# quad7seg.net
KiCad netlist of a schematic drawn in EAGLE
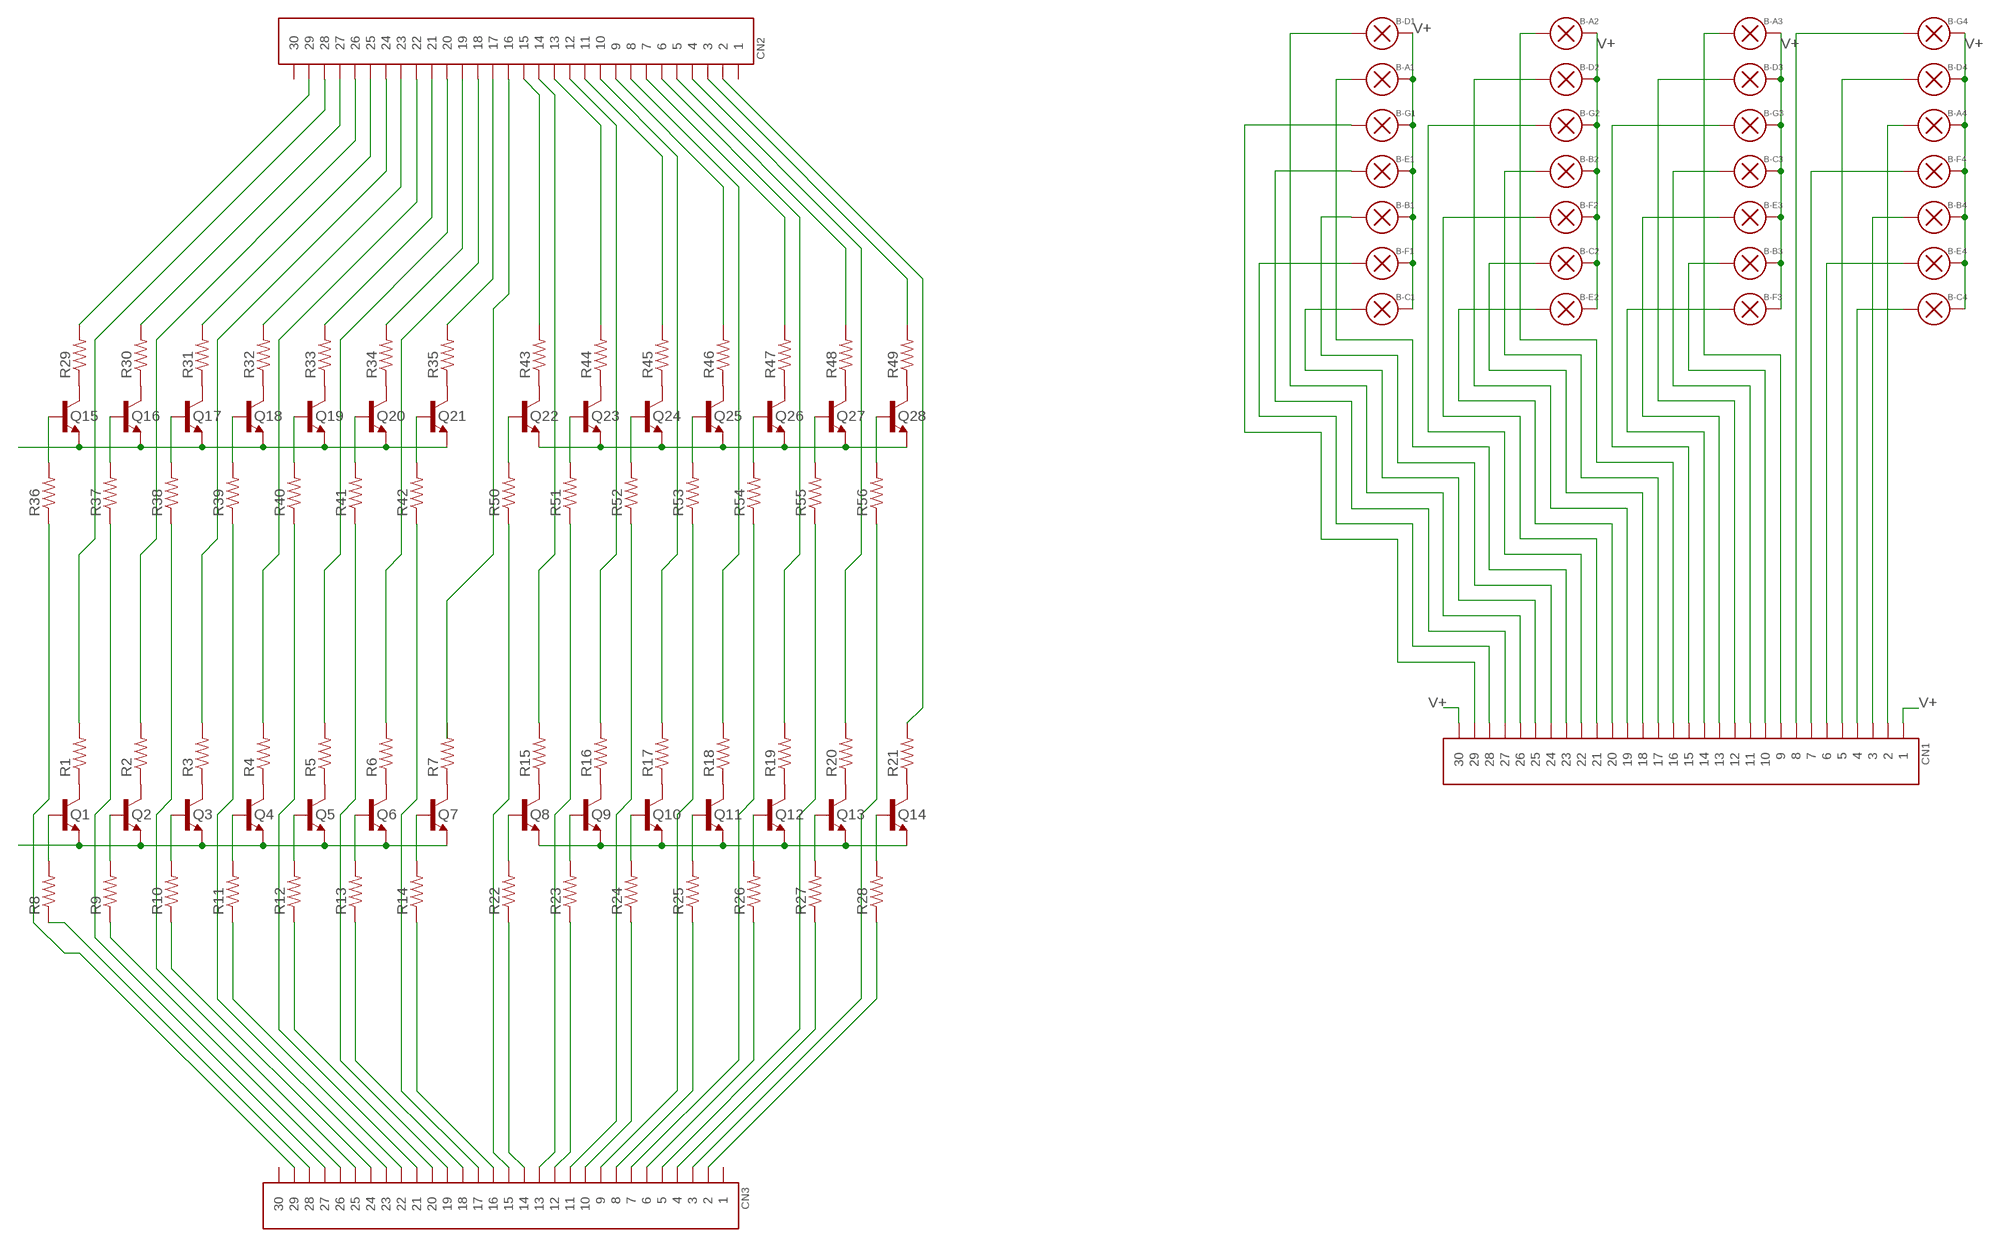
[diagram p0: schematic, sheet 1]

(export (version "E")
  (design (tool "Eeschema 10.0.6"))
  (components
    (comp (ref "B-A1")
      (value "BULB-N")
      (footprint "eagle-import:4X11BULB1")
      (libsource (lib "eagle-import") (part "BULB-N"))
    )
    (comp (ref "B-A2")
      (value "BULB-N")
      (footprint "eagle-import:4X11BULB1")
      (libsource (lib "eagle-import") (part "BULB-N"))
    )
    (comp (ref "B-A3")
      (value "BULB-N")
      (footprint "eagle-import:4X11BULB1")
      (libsource (lib "eagle-import") (part "BULB-N"))
    )
    (comp (ref "B-A4")
      (value "BULB-N")
      (footprint "eagle-import:4X11BULB1")
      (libsource (lib "eagle-import") (part "BULB-N"))
    )
    (comp (ref "B-B1")
      (value "BULB-F")
      (footprint "eagle-import:4X11BULB2")
      (libsource (lib "eagle-import") (part "BULB-F"))
    )
    (comp (ref "B-B2")
      (value "BULB-F")
      (footprint "eagle-import:4X11BULB2")
      (libsource (lib "eagle-import") (part "BULB-F"))
    )
    (comp (ref "B-B3")
      (value "BULB-F")
      (footprint "eagle-import:4X11BULB2")
      (libsource (lib "eagle-import") (part "BULB-F"))
    )
    (comp (ref "B-B4")
      (value "BULB-F")
      (footprint "eagle-import:4X11BULB2")
      (libsource (lib "eagle-import") (part "BULB-F"))
    )
    (comp (ref "B-C1")
      (value "BULB-F")
      (footprint "eagle-import:4X11BULB2")
      (libsource (lib "eagle-import") (part "BULB-F"))
    )
    (comp (ref "B-C2")
      (value "BULB-F")
      (footprint "eagle-import:4X11BULB2")
      (libsource (lib "eagle-import") (part "BULB-F"))
    )
    (comp (ref "B-C3")
      (value "BULB-F")
      (footprint "eagle-import:4X11BULB2")
      (libsource (lib "eagle-import") (part "BULB-F"))
    )
    (comp (ref "B-C4")
      (value "BULB-F")
      (footprint "eagle-import:4X11BULB2")
      (libsource (lib "eagle-import") (part "BULB-F"))
    )
    (comp (ref "B-D1")
      (value "BULB-N")
      (footprint "eagle-import:4X11BULB1")
      (libsource (lib "eagle-import") (part "BULB-N"))
    )
    (comp (ref "B-D2")
      (value "BULB-N")
      (footprint "eagle-import:4X11BULB1")
      (libsource (lib "eagle-import") (part "BULB-N"))
    )
    (comp (ref "B-D3")
      (value "BULB-N")
      (footprint "eagle-import:4X11BULB1")
      (libsource (lib "eagle-import") (part "BULB-N"))
    )
    (comp (ref "B-D4")
      (value "BULB-N")
      (footprint "eagle-import:4X11BULB1")
      (libsource (lib "eagle-import") (part "BULB-N"))
    )
    (comp (ref "B-E1")
      (value "BULB-F")
      (footprint "eagle-import:4X11BULB2")
      (libsource (lib "eagle-import") (part "BULB-F"))
    )
    (comp (ref "B-E2")
      (value "BULB-F")
      (footprint "eagle-import:4X11BULB2")
      (libsource (lib "eagle-import") (part "BULB-F"))
    )
    (comp (ref "B-E3")
      (value "BULB-F")
      (footprint "eagle-import:4X11BULB2")
      (libsource (lib "eagle-import") (part "BULB-F"))
    )
    (comp (ref "B-E4")
      (value "BULB-F")
      (footprint "eagle-import:4X11BULB2")
      (libsource (lib "eagle-import") (part "BULB-F"))
    )
    (comp (ref "B-F1")
      (value "BULB-F")
      (footprint "eagle-import:4X11BULB2")
      (libsource (lib "eagle-import") (part "BULB-F"))
    )
    (comp (ref "B-F2")
      (value "BULB-F")
      (footprint "eagle-import:4X11BULB2")
      (libsource (lib "eagle-import") (part "BULB-F"))
    )
    (comp (ref "B-F3")
      (value "BULB-F")
      (footprint "eagle-import:4X11BULB2")
      (libsource (lib "eagle-import") (part "BULB-F"))
    )
    (comp (ref "B-F4")
      (value "BULB-F")
      (footprint "eagle-import:4X11BULB2")
      (libsource (lib "eagle-import") (part "BULB-F"))
    )
    (comp (ref "B-G1")
      (value "BULB-N")
      (footprint "eagle-import:4X11BULB1")
      (libsource (lib "eagle-import") (part "BULB-N"))
    )
    (comp (ref "B-G2")
      (value "BULB-N")
      (footprint "eagle-import:4X11BULB1")
      (libsource (lib "eagle-import") (part "BULB-N"))
    )
    (comp (ref "B-G3")
      (value "BULB-N")
      (footprint "eagle-import:4X11BULB1")
      (libsource (lib "eagle-import") (part "BULB-N"))
    )
    (comp (ref "B-G4")
      (value "BULB-N")
      (footprint "eagle-import:4X11BULB1")
      (libsource (lib "eagle-import") (part "BULB-N"))
    )
    (comp (ref "CN1")
      (value "HD30")
      (footprint "eagle-import:HD30")
      (libsource (lib "eagle-import") (part "HD30"))
    )
    (comp (ref "CN2")
      (value "HD30")
      (footprint "eagle-import:HD30")
      (libsource (lib "eagle-import") (part "HD30"))
    )
    (comp (ref "CN3")
      (value "HD30")
      (footprint "eagle-import:HD30")
      (libsource (lib "eagle-import") (part "HD30"))
    )
    (comp (ref "Q1")
      (value "2N3904-1")
      (footprint "eagle-import:TO92BH")
      (libsource (lib "eagle-import") (part "2N3904-1"))
    )
    (comp (ref "Q2")
      (value "2N3904-1")
      (footprint "eagle-import:TO92BH")
      (libsource (lib "eagle-import") (part "2N3904-1"))
    )
    (comp (ref "Q3")
      (value "2N3904-1")
      (footprint "eagle-import:TO92BH")
      (libsource (lib "eagle-import") (part "2N3904-1"))
    )
    (comp (ref "Q4")
      (value "2N3904-1")
      (footprint "eagle-import:TO92BH")
      (libsource (lib "eagle-import") (part "2N3904-1"))
    )
    (comp (ref "Q5")
      (value "2N3904-1")
      (footprint "eagle-import:TO92BH")
      (libsource (lib "eagle-import") (part "2N3904-1"))
    )
    (comp (ref "Q6")
      (value "2N3904-1")
      (footprint "eagle-import:TO92BH")
      (libsource (lib "eagle-import") (part "2N3904-1"))
    )
    (comp (ref "Q7")
      (value "2N3904-1")
      (footprint "eagle-import:TO92BH")
      (libsource (lib "eagle-import") (part "2N3904-1"))
    )
    (comp (ref "Q8")
      (value "2N3904-1")
      (footprint "eagle-import:TO92BH")
      (libsource (lib "eagle-import") (part "2N3904-1"))
    )
    (comp (ref "Q9")
      (value "2N3904-1")
      (footprint "eagle-import:TO92BH")
      (libsource (lib "eagle-import") (part "2N3904-1"))
    )
    (comp (ref "Q10")
      (value "2N3904-1")
      (footprint "eagle-import:TO92BH")
      (libsource (lib "eagle-import") (part "2N3904-1"))
    )
    (comp (ref "Q11")
      (value "2N3904-1")
      (footprint "eagle-import:TO92BH")
      (libsource (lib "eagle-import") (part "2N3904-1"))
    )
    (comp (ref "Q12")
      (value "2N3904-1")
      (footprint "eagle-import:TO92BH")
      (libsource (lib "eagle-import") (part "2N3904-1"))
    )
    (comp (ref "Q13")
      (value "2N3904-1")
      (footprint "eagle-import:TO92BH")
      (libsource (lib "eagle-import") (part "2N3904-1"))
    )
    (comp (ref "Q14")
      (value "2N3904-1")
      (footprint "eagle-import:TO92BH")
      (libsource (lib "eagle-import") (part "2N3904-1"))
    )
    (comp (ref "Q15")
      (value "2N3904-1")
      (footprint "eagle-import:TO92BH")
      (libsource (lib "eagle-import") (part "2N3904-1"))
    )
    (comp (ref "Q16")
      (value "2N3904-1")
      (footprint "eagle-import:TO92BH")
      (libsource (lib "eagle-import") (part "2N3904-1"))
    )
    (comp (ref "Q17")
      (value "2N3904-1")
      (footprint "eagle-import:TO92BH")
      (libsource (lib "eagle-import") (part "2N3904-1"))
    )
    (comp (ref "Q18")
      (value "2N3904-1")
      (footprint "eagle-import:TO92BH")
      (libsource (lib "eagle-import") (part "2N3904-1"))
    )
    (comp (ref "Q19")
      (value "2N3904-1")
      (footprint "eagle-import:TO92BH")
      (libsource (lib "eagle-import") (part "2N3904-1"))
    )
    (comp (ref "Q20")
      (value "2N3904-1")
      (footprint "eagle-import:TO92BH")
      (libsource (lib "eagle-import") (part "2N3904-1"))
    )
    (comp (ref "Q21")
      (value "2N3904-1")
      (footprint "eagle-import:TO92BH")
      (libsource (lib "eagle-import") (part "2N3904-1"))
    )
    (comp (ref "Q22")
      (value "2N3904-1")
      (footprint "eagle-import:TO92BH")
      (libsource (lib "eagle-import") (part "2N3904-1"))
    )
    (comp (ref "Q23")
      (value "2N3904-1")
      (footprint "eagle-import:TO92BH")
      (libsource (lib "eagle-import") (part "2N3904-1"))
    )
    (comp (ref "Q24")
      (value "2N3904-1")
      (footprint "eagle-import:TO92BH")
      (libsource (lib "eagle-import") (part "2N3904-1"))
    )
    (comp (ref "Q25")
      (value "2N3904-1")
      (footprint "eagle-import:TO92BH")
      (libsource (lib "eagle-import") (part "2N3904-1"))
    )
    (comp (ref "Q26")
      (value "2N3904-1")
      (footprint "eagle-import:TO92BH")
      (libsource (lib "eagle-import") (part "2N3904-1"))
    )
    (comp (ref "Q27")
      (value "2N3904-1")
      (footprint "eagle-import:TO92BH")
      (libsource (lib "eagle-import") (part "2N3904-1"))
    )
    (comp (ref "Q28")
      (value "2N3904-1")
      (footprint "eagle-import:TO92BH")
      (libsource (lib "eagle-import") (part "2N3904-1"))
    )
    (comp (ref "R1")
      (value "R1/8-7.6MM")
      (footprint "eagle-import:R0125-7.6")
      (libsource (lib "eagle-import") (part "R1/8-7.6MM"))
    )
    (comp (ref "R2")
      (value "R1/8-7.6MM")
      (footprint "eagle-import:R0125-7.6")
      (libsource (lib "eagle-import") (part "R1/8-7.6MM"))
    )
    (comp (ref "R3")
      (value "R1/8-7.6MM")
      (footprint "eagle-import:R0125-7.6")
      (libsource (lib "eagle-import") (part "R1/8-7.6MM"))
    )
    (comp (ref "R4")
      (value "R1/8-7.6MM")
      (footprint "eagle-import:R0125-7.6")
      (libsource (lib "eagle-import") (part "R1/8-7.6MM"))
    )
    (comp (ref "R5")
      (value "R1/8-7.6MM")
      (footprint "eagle-import:R0125-7.6")
      (libsource (lib "eagle-import") (part "R1/8-7.6MM"))
    )
    (comp (ref "R6")
      (value "R1/8-7.6MM")
      (footprint "eagle-import:R0125-7.6")
      (libsource (lib "eagle-import") (part "R1/8-7.6MM"))
    )
    (comp (ref "R7")
      (value "R1/8-7.6MM")
      (footprint "eagle-import:R0125-7.6")
      (libsource (lib "eagle-import") (part "R1/8-7.6MM"))
    )
    (comp (ref "R8")
      (value "R1/8-7.6MM")
      (footprint "eagle-import:R0125-7.6")
      (libsource (lib "eagle-import") (part "R1/8-7.6MM"))
    )
    (comp (ref "R9")
      (value "R1/8-7.6MM")
      (footprint "eagle-import:R0125-7.6")
      (libsource (lib "eagle-import") (part "R1/8-7.6MM"))
    )
    (comp (ref "R10")
      (value "R1/8-7.6MM")
      (footprint "eagle-import:R0125-7.6")
      (libsource (lib "eagle-import") (part "R1/8-7.6MM"))
    )
    (comp (ref "R11")
      (value "R1/8-7.6MM")
      (footprint "eagle-import:R0125-7.6")
      (libsource (lib "eagle-import") (part "R1/8-7.6MM"))
    )
    (comp (ref "R12")
      (value "R1/8-7.6MM")
      (footprint "eagle-import:R0125-7.6")
      (libsource (lib "eagle-import") (part "R1/8-7.6MM"))
    )
    (comp (ref "R13")
      (value "R1/8-7.6MM")
      (footprint "eagle-import:R0125-7.6")
      (libsource (lib "eagle-import") (part "R1/8-7.6MM"))
    )
    (comp (ref "R14")
      (value "R1/8-7.6MM")
      (footprint "eagle-import:R0125-7.6")
      (libsource (lib "eagle-import") (part "R1/8-7.6MM"))
    )
    (comp (ref "R15")
      (value "R1/8-7.6MM")
      (footprint "eagle-import:R0125-7.6")
      (libsource (lib "eagle-import") (part "R1/8-7.6MM"))
    )
    (comp (ref "R16")
      (value "R1/8-7.6MM")
      (footprint "eagle-import:R0125-7.6")
      (libsource (lib "eagle-import") (part "R1/8-7.6MM"))
    )
    (comp (ref "R17")
      (value "R1/8-7.6MM")
      (footprint "eagle-import:R0125-7.6")
      (libsource (lib "eagle-import") (part "R1/8-7.6MM"))
    )
    (comp (ref "R18")
      (value "R1/8-7.6MM")
      (footprint "eagle-import:R0125-7.6")
      (libsource (lib "eagle-import") (part "R1/8-7.6MM"))
    )
    (comp (ref "R19")
      (value "R1/8-7.6MM")
      (footprint "eagle-import:R0125-7.6")
      (libsource (lib "eagle-import") (part "R1/8-7.6MM"))
    )
    (comp (ref "R20")
      (value "R1/8-7.6MM")
      (footprint "eagle-import:R0125-7.6")
      (libsource (lib "eagle-import") (part "R1/8-7.6MM"))
    )
    (comp (ref "R21")
      (value "R1/8-7.6MM")
      (footprint "eagle-import:R0125-7.6")
      (libsource (lib "eagle-import") (part "R1/8-7.6MM"))
    )
    (comp (ref "R22")
      (value "R1/8-7.6MM")
      (footprint "eagle-import:R0125-7.6")
      (libsource (lib "eagle-import") (part "R1/8-7.6MM"))
    )
    (comp (ref "R23")
      (value "R1/8-7.6MM")
      (footprint "eagle-import:R0125-7.6")
      (libsource (lib "eagle-import") (part "R1/8-7.6MM"))
    )
    (comp (ref "R24")
      (value "R1/8-7.6MM")
      (footprint "eagle-import:R0125-7.6")
      (libsource (lib "eagle-import") (part "R1/8-7.6MM"))
    )
    (comp (ref "R25")
      (value "R1/8-7.6MM")
      (footprint "eagle-import:R0125-7.6")
      (libsource (lib "eagle-import") (part "R1/8-7.6MM"))
    )
    (comp (ref "R26")
      (value "R1/8-7.6MM")
      (footprint "eagle-import:R0125-7.6")
      (libsource (lib "eagle-import") (part "R1/8-7.6MM"))
    )
    (comp (ref "R27")
      (value "R1/8-7.6MM")
      (footprint "eagle-import:R0125-7.6")
      (libsource (lib "eagle-import") (part "R1/8-7.6MM"))
    )
    (comp (ref "R28")
      (value "R1/8-7.6MM")
      (footprint "eagle-import:R0125-7.6")
      (libsource (lib "eagle-import") (part "R1/8-7.6MM"))
    )
    (comp (ref "R29")
      (value "R1/8-7.6MM")
      (footprint "eagle-import:R0125-7.6")
      (libsource (lib "eagle-import") (part "R1/8-7.6MM"))
    )
    (comp (ref "R30")
      (value "R1/8-7.6MM")
      (footprint "eagle-import:R0125-7.6")
      (libsource (lib "eagle-import") (part "R1/8-7.6MM"))
    )
    (comp (ref "R31")
      (value "R1/8-7.6MM")
      (footprint "eagle-import:R0125-7.6")
      (libsource (lib "eagle-import") (part "R1/8-7.6MM"))
    )
    (comp (ref "R32")
      (value "R1/8-7.6MM")
      (footprint "eagle-import:R0125-7.6")
      (libsource (lib "eagle-import") (part "R1/8-7.6MM"))
    )
    (comp (ref "R33")
      (value "R1/8-7.6MM")
      (footprint "eagle-import:R0125-7.6")
      (libsource (lib "eagle-import") (part "R1/8-7.6MM"))
    )
    (comp (ref "R34")
      (value "R1/8-7.6MM")
      (footprint "eagle-import:R0125-7.6")
      (libsource (lib "eagle-import") (part "R1/8-7.6MM"))
    )
    (comp (ref "R35")
      (value "R1/8-7.6MM")
      (footprint "eagle-import:R0125-7.6")
      (libsource (lib "eagle-import") (part "R1/8-7.6MM"))
    )
    (comp (ref "R36")
      (value "R1/8-7.6MM")
      (footprint "eagle-import:R0125-7.6")
      (libsource (lib "eagle-import") (part "R1/8-7.6MM"))
    )
    (comp (ref "R37")
      (value "R1/8-7.6MM")
      (footprint "eagle-import:R0125-7.6")
      (libsource (lib "eagle-import") (part "R1/8-7.6MM"))
    )
    (comp (ref "R38")
      (value "R1/8-7.6MM")
      (footprint "eagle-import:R0125-7.6")
      (libsource (lib "eagle-import") (part "R1/8-7.6MM"))
    )
    (comp (ref "R39")
      (value "R1/8-7.6MM")
      (footprint "eagle-import:R0125-7.6")
      (libsource (lib "eagle-import") (part "R1/8-7.6MM"))
    )
    (comp (ref "R40")
      (value "R1/8-7.6MM")
      (footprint "eagle-import:R0125-7.6")
      (libsource (lib "eagle-import") (part "R1/8-7.6MM"))
    )
    (comp (ref "R41")
      (value "R1/8-7.6MM")
      (footprint "eagle-import:R0125-7.6")
      (libsource (lib "eagle-import") (part "R1/8-7.6MM"))
    )
    (comp (ref "R42")
      (value "R1/8-7.6MM")
      (footprint "eagle-import:R0125-7.6")
      (libsource (lib "eagle-import") (part "R1/8-7.6MM"))
    )
    (comp (ref "R43")
      (value "R1/8-7.6MM")
      (footprint "eagle-import:R0125-7.6")
      (libsource (lib "eagle-import") (part "R1/8-7.6MM"))
    )
    (comp (ref "R44")
      (value "R1/8-7.6MM")
      (footprint "eagle-import:R0125-7.6")
      (libsource (lib "eagle-import") (part "R1/8-7.6MM"))
    )
    (comp (ref "R45")
      (value "R1/8-7.6MM")
      (footprint "eagle-import:R0125-7.6")
      (libsource (lib "eagle-import") (part "R1/8-7.6MM"))
    )
    (comp (ref "R46")
      (value "R1/8-7.6MM")
      (footprint "eagle-import:R0125-7.6")
      (libsource (lib "eagle-import") (part "R1/8-7.6MM"))
    )
    (comp (ref "R47")
      (value "R1/8-7.6MM")
      (footprint "eagle-import:R0125-7.6")
      (libsource (lib "eagle-import") (part "R1/8-7.6MM"))
    )
    (comp (ref "R48")
      (value "R1/8-7.6MM")
      (footprint "eagle-import:R0125-7.6")
      (libsource (lib "eagle-import") (part "R1/8-7.6MM"))
    )
    (comp (ref "R49")
      (value "R1/8-7.6MM")
      (footprint "eagle-import:R0125-7.6")
      (libsource (lib "eagle-import") (part "R1/8-7.6MM"))
    )
    (comp (ref "R50")
      (value "R1/8-7.6MM")
      (footprint "eagle-import:R0125-7.6")
      (libsource (lib "eagle-import") (part "R1/8-7.6MM"))
    )
    (comp (ref "R51")
      (value "R1/8-7.6MM")
      (footprint "eagle-import:R0125-7.6")
      (libsource (lib "eagle-import") (part "R1/8-7.6MM"))
    )
    (comp (ref "R52")
      (value "R1/8-7.6MM")
      (footprint "eagle-import:R0125-7.6")
      (libsource (lib "eagle-import") (part "R1/8-7.6MM"))
    )
    (comp (ref "R53")
      (value "R1/8-7.6MM")
      (footprint "eagle-import:R0125-7.6")
      (libsource (lib "eagle-import") (part "R1/8-7.6MM"))
    )
    (comp (ref "R54")
      (value "R1/8-7.6MM")
      (footprint "eagle-import:R0125-7.6")
      (libsource (lib "eagle-import") (part "R1/8-7.6MM"))
    )
    (comp (ref "R55")
      (value "R1/8-7.6MM")
      (footprint "eagle-import:R0125-7.6")
      (libsource (lib "eagle-import") (part "R1/8-7.6MM"))
    )
    (comp (ref "R56")
      (value "R1/8-7.6MM")
      (footprint "eagle-import:R0125-7.6")
      (libsource (lib "eagle-import") (part "R1/8-7.6MM"))
    )
  )
  (nets
    (net (code "1") (name "/GND") (class "Default")
      (node (ref "Q1") (pin "1") (pinfunction "E_1") (pintype "passive"))
      (node (ref "Q10") (pin "1") (pinfunction "E_1") (pintype "passive"))
      (node (ref "Q11") (pin "1") (pinfunction "E_1") (pintype "passive"))
      (node (ref "Q12") (pin "1") (pinfunction "E_1") (pintype "passive"))
      (node (ref "Q13") (pin "1") (pinfunction "E_1") (pintype "passive"))
      (node (ref "Q14") (pin "1") (pinfunction "E_1") (pintype "passive"))
      (node (ref "Q15") (pin "1") (pinfunction "E_1") (pintype "passive"))
      (node (ref "Q16") (pin "1") (pinfunction "E_1") (pintype "passive"))
      (node (ref "Q17") (pin "1") (pinfunction "E_1") (pintype "passive"))
      (node (ref "Q18") (pin "1") (pinfunction "E_1") (pintype "passive"))
      (node (ref "Q19") (pin "1") (pinfunction "E_1") (pintype "passive"))
      (node (ref "Q2") (pin "1") (pinfunction "E_1") (pintype "passive"))
      (node (ref "Q20") (pin "1") (pinfunction "E_1") (pintype "passive"))
      (node (ref "Q21") (pin "1") (pinfunction "E_1") (pintype "passive"))
      (node (ref "Q22") (pin "1") (pinfunction "E_1") (pintype "passive"))
      (node (ref "Q23") (pin "1") (pinfunction "E_1") (pintype "passive"))
      (node (ref "Q24") (pin "1") (pinfunction "E_1") (pintype "passive"))
      (node (ref "Q25") (pin "1") (pinfunction "E_1") (pintype "passive"))
      (node (ref "Q26") (pin "1") (pinfunction "E_1") (pintype "passive"))
      (node (ref "Q27") (pin "1") (pinfunction "E_1") (pintype "passive"))
      (node (ref "Q28") (pin "1") (pinfunction "E_1") (pintype "passive"))
      (node (ref "Q3") (pin "1") (pinfunction "E_1") (pintype "passive"))
      (node (ref "Q4") (pin "1") (pinfunction "E_1") (pintype "passive"))
      (node (ref "Q5") (pin "1") (pinfunction "E_1") (pintype "passive"))
      (node (ref "Q6") (pin "1") (pinfunction "E_1") (pintype "passive"))
      (node (ref "Q7") (pin "1") (pinfunction "E_1") (pintype "passive"))
      (node (ref "Q8") (pin "1") (pinfunction "E_1") (pintype "passive"))
      (node (ref "Q9") (pin "1") (pinfunction "E_1") (pintype "passive"))
    )
    (net (code "2") (name "/V+") (class "Default")
      (node (ref "B-A1") (pin "P$2") (pinfunction "P$2_P$2") (pintype "bidirectional"))
      (node (ref "B-A2") (pin "P$2") (pinfunction "P$2_P$2") (pintype "bidirectional"))
      (node (ref "B-A3") (pin "P$2") (pinfunction "P$2_P$2") (pintype "bidirectional"))
      (node (ref "B-A4") (pin "P$2") (pinfunction "P$2_P$2") (pintype "bidirectional"))
      (node (ref "B-B1") (pin "P$2") (pinfunction "P$2_P$2") (pintype "bidirectional"))
      (node (ref "B-B2") (pin "P$2") (pinfunction "P$2_P$2") (pintype "bidirectional"))
      (node (ref "B-B3") (pin "P$2") (pinfunction "P$2_P$2") (pintype "bidirectional"))
      (node (ref "B-B4") (pin "P$2") (pinfunction "P$2_P$2") (pintype "bidirectional"))
      (node (ref "B-C1") (pin "P$2") (pinfunction "P$2_P$2") (pintype "bidirectional"))
      (node (ref "B-C2") (pin "P$2") (pinfunction "P$2_P$2") (pintype "bidirectional"))
      (node (ref "B-C3") (pin "P$2") (pinfunction "P$2_P$2") (pintype "bidirectional"))
      (node (ref "B-C4") (pin "P$2") (pinfunction "P$2_P$2") (pintype "bidirectional"))
      (node (ref "B-D1") (pin "P$2") (pinfunction "P$2_P$2") (pintype "bidirectional"))
      (node (ref "B-D2") (pin "P$2") (pinfunction "P$2_P$2") (pintype "bidirectional"))
      (node (ref "B-D3") (pin "P$2") (pinfunction "P$2_P$2") (pintype "bidirectional"))
      (node (ref "B-D4") (pin "P$2") (pinfunction "P$2_P$2") (pintype "bidirectional"))
      (node (ref "B-E1") (pin "P$2") (pinfunction "P$2_P$2") (pintype "bidirectional"))
      (node (ref "B-E2") (pin "P$2") (pinfunction "P$2_P$2") (pintype "bidirectional"))
      (node (ref "B-E3") (pin "P$2") (pinfunction "P$2_P$2") (pintype "bidirectional"))
      (node (ref "B-E4") (pin "P$2") (pinfunction "P$2_P$2") (pintype "bidirectional"))
      (node (ref "B-F1") (pin "P$2") (pinfunction "P$2_P$2") (pintype "bidirectional"))
      (node (ref "B-F2") (pin "P$2") (pinfunction "P$2_P$2") (pintype "bidirectional"))
      (node (ref "B-F3") (pin "P$2") (pinfunction "P$2_P$2") (pintype "bidirectional"))
      (node (ref "B-F4") (pin "P$2") (pinfunction "P$2_P$2") (pintype "bidirectional"))
      (node (ref "B-G1") (pin "P$2") (pinfunction "P$2_P$2") (pintype "bidirectional"))
      (node (ref "B-G2") (pin "P$2") (pinfunction "P$2_P$2") (pintype "bidirectional"))
      (node (ref "B-G3") (pin "P$2") (pinfunction "P$2_P$2") (pintype "bidirectional"))
      (node (ref "B-G4") (pin "P$2") (pinfunction "P$2_P$2") (pintype "bidirectional"))
      (node (ref "CN1") (pin "P$1") (pinfunction "1_P$1") (pintype "bidirectional"))
      (node (ref "CN1") (pin "P$30") (pinfunction "30_P$30") (pintype "bidirectional"))
    )
    (net (code "3") (name "Net-(CN1-2)") (class "Default")
      (node (ref "B-A4") (pin "P$1") (pinfunction "P$1_P$1") (pintype "bidirectional"))
      (node (ref "CN1") (pin "P$2") (pinfunction "2_P$2") (pintype "bidirectional"))
    )
    (net (code "4") (name "Net-(CN1-3)") (class "Default")
      (node (ref "B-B4") (pin "P$1") (pinfunction "P$1_P$1") (pintype "bidirectional"))
      (node (ref "CN1") (pin "P$3") (pinfunction "3_P$3") (pintype "bidirectional"))
    )
    (net (code "5") (name "Net-(CN1-4)") (class "Default")
      (node (ref "B-C4") (pin "P$1") (pinfunction "P$1_P$1") (pintype "bidirectional"))
      (node (ref "CN1") (pin "P$4") (pinfunction "4_P$4") (pintype "bidirectional"))
    )
    (net (code "6") (name "Net-(CN1-5)") (class "Default")
      (node (ref "B-D4") (pin "P$1") (pinfunction "P$1_P$1") (pintype "bidirectional"))
      (node (ref "CN1") (pin "P$5") (pinfunction "5_P$5") (pintype "bidirectional"))
    )
    (net (code "7") (name "Net-(CN1-6)") (class "Default")
      (node (ref "B-E4") (pin "P$1") (pinfunction "P$1_P$1") (pintype "bidirectional"))
      (node (ref "CN1") (pin "P$6") (pinfunction "6_P$6") (pintype "bidirectional"))
    )
    (net (code "8") (name "Net-(CN1-7)") (class "Default")
      (node (ref "B-F4") (pin "P$1") (pinfunction "P$1_P$1") (pintype "bidirectional"))
      (node (ref "CN1") (pin "P$7") (pinfunction "7_P$7") (pintype "bidirectional"))
    )
    (net (code "9") (name "Net-(CN1-8)") (class "Default")
      (node (ref "B-G4") (pin "P$1") (pinfunction "P$1_P$1") (pintype "bidirectional"))
      (node (ref "CN1") (pin "P$8") (pinfunction "8_P$8") (pintype "bidirectional"))
    )
    (net (code "10") (name "Net-(CN1-9)") (class "Default")
      (node (ref "B-A3") (pin "P$1") (pinfunction "P$1_P$1") (pintype "bidirectional"))
      (node (ref "CN1") (pin "P$9") (pinfunction "9_P$9") (pintype "bidirectional"))
    )
    (net (code "11") (name "Net-(CN1-10)") (class "Default")
      (node (ref "B-B3") (pin "P$1") (pinfunction "P$1_P$1") (pintype "bidirectional"))
      (node (ref "CN1") (pin "P$10") (pinfunction "10_P$10") (pintype "bidirectional"))
    )
    (net (code "12") (name "Net-(CN1-11)") (class "Default")
      (node (ref "B-C3") (pin "P$1") (pinfunction "P$1_P$1") (pintype "bidirectional"))
      (node (ref "CN1") (pin "P$11") (pinfunction "11_P$11") (pintype "bidirectional"))
    )
    (net (code "13") (name "Net-(CN1-12)") (class "Default")
      (node (ref "B-D3") (pin "P$1") (pinfunction "P$1_P$1") (pintype "bidirectional"))
      (node (ref "CN1") (pin "P$12") (pinfunction "12_P$12") (pintype "bidirectional"))
    )
    (net (code "14") (name "Net-(CN1-13)") (class "Default")
      (node (ref "B-E3") (pin "P$1") (pinfunction "P$1_P$1") (pintype "bidirectional"))
      (node (ref "CN1") (pin "P$13") (pinfunction "13_P$13") (pintype "bidirectional"))
    )
    (net (code "15") (name "Net-(CN1-14)") (class "Default")
      (node (ref "B-F3") (pin "P$1") (pinfunction "P$1_P$1") (pintype "bidirectional"))
      (node (ref "CN1") (pin "P$14") (pinfunction "14_P$14") (pintype "bidirectional"))
    )
    (net (code "16") (name "Net-(CN1-15)") (class "Default")
      (node (ref "B-G3") (pin "P$1") (pinfunction "P$1_P$1") (pintype "bidirectional"))
      (node (ref "CN1") (pin "P$15") (pinfunction "15_P$15") (pintype "bidirectional"))
    )
    (net (code "17") (name "Net-(CN1-16)") (class "Default")
      (node (ref "B-A2") (pin "P$1") (pinfunction "P$1_P$1") (pintype "bidirectional"))
      (node (ref "CN1") (pin "P$16") (pinfunction "16_P$16") (pintype "bidirectional"))
    )
    (net (code "18") (name "Net-(CN1-17)") (class "Default")
      (node (ref "B-B2") (pin "P$1") (pinfunction "P$1_P$1") (pintype "bidirectional"))
      (node (ref "CN1") (pin "P$17") (pinfunction "17_P$17") (pintype "bidirectional"))
    )
    (net (code "19") (name "Net-(CN1-18)") (class "Default")
      (node (ref "B-C2") (pin "P$1") (pinfunction "P$1_P$1") (pintype "bidirectional"))
      (node (ref "CN1") (pin "P$18") (pinfunction "18_P$18") (pintype "bidirectional"))
    )
    (net (code "20") (name "Net-(CN1-19)") (class "Default")
      (node (ref "B-D2") (pin "P$1") (pinfunction "P$1_P$1") (pintype "bidirectional"))
      (node (ref "CN1") (pin "P$19") (pinfunction "19_P$19") (pintype "bidirectional"))
    )
    (net (code "21") (name "Net-(CN1-20)") (class "Default")
      (node (ref "B-E2") (pin "P$1") (pinfunction "P$1_P$1") (pintype "bidirectional"))
      (node (ref "CN1") (pin "P$20") (pinfunction "20_P$20") (pintype "bidirectional"))
    )
    (net (code "22") (name "Net-(CN1-21)") (class "Default")
      (node (ref "B-F2") (pin "P$1") (pinfunction "P$1_P$1") (pintype "bidirectional"))
      (node (ref "CN1") (pin "P$21") (pinfunction "21_P$21") (pintype "bidirectional"))
    )
    (net (code "23") (name "Net-(CN1-22)") (class "Default")
      (node (ref "B-G2") (pin "P$1") (pinfunction "P$1_P$1") (pintype "bidirectional"))
      (node (ref "CN1") (pin "P$22") (pinfunction "22_P$22") (pintype "bidirectional"))
    )
    (net (code "24") (name "Net-(CN1-23)") (class "Default")
      (node (ref "B-A1") (pin "P$1") (pinfunction "P$1_P$1") (pintype "bidirectional"))
      (node (ref "CN1") (pin "P$23") (pinfunction "23_P$23") (pintype "bidirectional"))
    )
    (net (code "25") (name "Net-(CN1-24)") (class "Default")
      (node (ref "B-B1") (pin "P$1") (pinfunction "P$1_P$1") (pintype "bidirectional"))
      (node (ref "CN1") (pin "P$24") (pinfunction "24_P$24") (pintype "bidirectional"))
    )
    (net (code "26") (name "Net-(CN1-25)") (class "Default")
      (node (ref "B-C1") (pin "P$1") (pinfunction "P$1_P$1") (pintype "bidirectional"))
      (node (ref "CN1") (pin "P$25") (pinfunction "25_P$25") (pintype "bidirectional"))
    )
    (net (code "27") (name "Net-(CN1-26)") (class "Default")
      (node (ref "B-D1") (pin "P$1") (pinfunction "P$1_P$1") (pintype "bidirectional"))
      (node (ref "CN1") (pin "P$26") (pinfunction "26_P$26") (pintype "bidirectional"))
    )
    (net (code "28") (name "Net-(CN1-27)") (class "Default")
      (node (ref "B-E1") (pin "P$1") (pinfunction "P$1_P$1") (pintype "bidirectional"))
      (node (ref "CN1") (pin "P$27") (pinfunction "27_P$27") (pintype "bidirectional"))
    )
    (net (code "29") (name "Net-(CN1-28)") (class "Default")
      (node (ref "B-F1") (pin "P$1") (pinfunction "P$1_P$1") (pintype "bidirectional"))
      (node (ref "CN1") (pin "P$28") (pinfunction "28_P$28") (pintype "bidirectional"))
    )
    (net (code "30") (name "Net-(CN1-29)") (class "Default")
      (node (ref "B-G1") (pin "P$1") (pinfunction "P$1_P$1") (pintype "bidirectional"))
      (node (ref "CN1") (pin "P$29") (pinfunction "29_P$29") (pintype "bidirectional"))
    )
    (net (code "31") (name "Net-(CN2-2)") (class "Default")
      (node (ref "CN2") (pin "P$2") (pinfunction "2_P$2") (pintype "bidirectional"))
      (node (ref "R21") (pin "2") (pinfunction "2_2") (pintype "passive"))
    )
    (net (code "32") (name "Net-(CN2-3)") (class "Default")
      (node (ref "CN2") (pin "P$3") (pinfunction "3_P$3") (pintype "bidirectional"))
      (node (ref "R49") (pin "2") (pinfunction "2_2") (pintype "passive"))
    )
    (net (code "33") (name "Net-(CN2-4)") (class "Default")
      (node (ref "CN2") (pin "P$4") (pinfunction "4_P$4") (pintype "bidirectional"))
      (node (ref "R20") (pin "2") (pinfunction "2_2") (pintype "passive"))
    )
    (net (code "34") (name "Net-(CN2-5)") (class "Default")
      (node (ref "CN2") (pin "P$5") (pinfunction "5_P$5") (pintype "bidirectional"))
      (node (ref "R48") (pin "2") (pinfunction "2_2") (pintype "passive"))
    )
    (net (code "35") (name "Net-(CN2-6)") (class "Default")
      (node (ref "CN2") (pin "P$6") (pinfunction "6_P$6") (pintype "bidirectional"))
      (node (ref "R19") (pin "2") (pinfunction "2_2") (pintype "passive"))
    )
    (net (code "36") (name "Net-(CN2-7)") (class "Default")
      (node (ref "CN2") (pin "P$7") (pinfunction "7_P$7") (pintype "bidirectional"))
      (node (ref "R47") (pin "2") (pinfunction "2_2") (pintype "passive"))
    )
    (net (code "37") (name "Net-(CN2-8)") (class "Default")
      (node (ref "CN2") (pin "P$8") (pinfunction "8_P$8") (pintype "bidirectional"))
      (node (ref "R18") (pin "2") (pinfunction "2_2") (pintype "passive"))
    )
    (net (code "38") (name "Net-(CN2-9)") (class "Default")
      (node (ref "CN2") (pin "P$9") (pinfunction "9_P$9") (pintype "bidirectional"))
      (node (ref "R46") (pin "2") (pinfunction "2_2") (pintype "passive"))
    )
    (net (code "39") (name "Net-(CN2-10)") (class "Default")
      (node (ref "CN2") (pin "P$10") (pinfunction "10_P$10") (pintype "bidirectional"))
      (node (ref "R17") (pin "2") (pinfunction "2_2") (pintype "passive"))
    )
    (net (code "40") (name "Net-(CN2-11)") (class "Default")
      (node (ref "CN2") (pin "P$11") (pinfunction "11_P$11") (pintype "bidirectional"))
      (node (ref "R45") (pin "2") (pinfunction "2_2") (pintype "passive"))
    )
    (net (code "41") (name "Net-(CN2-12)") (class "Default")
      (node (ref "CN2") (pin "P$12") (pinfunction "12_P$12") (pintype "bidirectional"))
      (node (ref "R16") (pin "2") (pinfunction "2_2") (pintype "passive"))
    )
    (net (code "42") (name "Net-(CN2-13)") (class "Default")
      (node (ref "CN2") (pin "P$13") (pinfunction "13_P$13") (pintype "bidirectional"))
      (node (ref "R44") (pin "2") (pinfunction "2_2") (pintype "passive"))
    )
    (net (code "43") (name "Net-(CN2-14)") (class "Default")
      (node (ref "CN2") (pin "P$14") (pinfunction "14_P$14") (pintype "bidirectional"))
      (node (ref "R15") (pin "2") (pinfunction "2_2") (pintype "passive"))
    )
    (net (code "44") (name "Net-(CN2-15)") (class "Default")
      (node (ref "CN2") (pin "P$15") (pinfunction "15_P$15") (pintype "bidirectional"))
      (node (ref "R43") (pin "2") (pinfunction "2_2") (pintype "passive"))
    )
    (net (code "45") (name "Net-(CN2-17)") (class "Default")
      (node (ref "CN2") (pin "P$17") (pinfunction "17_P$17") (pintype "bidirectional"))
      (node (ref "R35") (pin "2") (pinfunction "2_2") (pintype "passive"))
    )
    (net (code "46") (name "Net-(CN2-18)") (class "Default")
      (node (ref "CN2") (pin "P$18") (pinfunction "18_P$18") (pintype "bidirectional"))
      (node (ref "R6") (pin "2") (pinfunction "2_2") (pintype "passive"))
    )
    (net (code "47") (name "Net-(CN2-19)") (class "Default")
      (node (ref "CN2") (pin "P$19") (pinfunction "19_P$19") (pintype "bidirectional"))
      (node (ref "R34") (pin "2") (pinfunction "2_2") (pintype "passive"))
    )
    (net (code "48") (name "Net-(CN2-20)") (class "Default")
      (node (ref "CN2") (pin "P$20") (pinfunction "20_P$20") (pintype "bidirectional"))
      (node (ref "R5") (pin "2") (pinfunction "2_2") (pintype "passive"))
    )
    (net (code "49") (name "Net-(CN2-21)") (class "Default")
      (node (ref "CN2") (pin "P$21") (pinfunction "21_P$21") (pintype "bidirectional"))
      (node (ref "R33") (pin "2") (pinfunction "2_2") (pintype "passive"))
    )
    (net (code "50") (name "Net-(CN2-22)") (class "Default")
      (node (ref "CN2") (pin "P$22") (pinfunction "22_P$22") (pintype "bidirectional"))
      (node (ref "R4") (pin "2") (pinfunction "2_2") (pintype "passive"))
    )
    (net (code "51") (name "Net-(CN2-23)") (class "Default")
      (node (ref "CN2") (pin "P$23") (pinfunction "23_P$23") (pintype "bidirectional"))
      (node (ref "R32") (pin "2") (pinfunction "2_2") (pintype "passive"))
    )
    (net (code "52") (name "Net-(CN2-24)") (class "Default")
      (node (ref "CN2") (pin "P$24") (pinfunction "24_P$24") (pintype "bidirectional"))
      (node (ref "R3") (pin "2") (pinfunction "2_2") (pintype "passive"))
    )
    (net (code "53") (name "Net-(CN2-25)") (class "Default")
      (node (ref "CN2") (pin "P$25") (pinfunction "25_P$25") (pintype "bidirectional"))
      (node (ref "R31") (pin "2") (pinfunction "2_2") (pintype "passive"))
    )
    (net (code "54") (name "Net-(CN2-26)") (class "Default")
      (node (ref "CN2") (pin "P$26") (pinfunction "26_P$26") (pintype "bidirectional"))
      (node (ref "R2") (pin "2") (pinfunction "2_2") (pintype "passive"))
    )
    (net (code "55") (name "Net-(CN2-27)") (class "Default")
      (node (ref "CN2") (pin "P$27") (pinfunction "27_P$27") (pintype "bidirectional"))
      (node (ref "R30") (pin "2") (pinfunction "2_2") (pintype "passive"))
    )
    (net (code "56") (name "Net-(CN2-28)") (class "Default")
      (node (ref "CN2") (pin "P$28") (pinfunction "28_P$28") (pintype "bidirectional"))
      (node (ref "R1") (pin "2") (pinfunction "2_2") (pintype "passive"))
    )
    (net (code "57") (name "Net-(CN2-29)") (class "Default")
      (node (ref "CN2") (pin "P$29") (pinfunction "29_P$29") (pintype "bidirectional"))
      (node (ref "R29") (pin "2") (pinfunction "2_2") (pintype "passive"))
    )
    (net (code "58") (name "Net-(CN3-2)") (class "Default")
      (node (ref "CN3") (pin "P$2") (pinfunction "2_P$2") (pintype "bidirectional"))
      (node (ref "R28") (pin "1") (pinfunction "1_1") (pintype "passive"))
    )
    (net (code "59") (name "Net-(CN3-3)") (class "Default")
      (node (ref "CN3") (pin "P$3") (pinfunction "3_P$3") (pintype "bidirectional"))
      (node (ref "R56") (pin "1") (pinfunction "1_1") (pintype "passive"))
    )
    (net (code "60") (name "Net-(CN3-4)") (class "Default")
      (node (ref "CN3") (pin "P$4") (pinfunction "4_P$4") (pintype "bidirectional"))
      (node (ref "R27") (pin "1") (pinfunction "1_1") (pintype "passive"))
    )
    (net (code "61") (name "Net-(CN3-5)") (class "Default")
      (node (ref "CN3") (pin "P$5") (pinfunction "5_P$5") (pintype "bidirectional"))
      (node (ref "R55") (pin "1") (pinfunction "1_1") (pintype "passive"))
    )
    (net (code "62") (name "Net-(CN3-6)") (class "Default")
      (node (ref "CN3") (pin "P$6") (pinfunction "6_P$6") (pintype "bidirectional"))
      (node (ref "R26") (pin "1") (pinfunction "1_1") (pintype "passive"))
    )
    (net (code "63") (name "Net-(CN3-7)") (class "Default")
      (node (ref "CN3") (pin "P$7") (pinfunction "7_P$7") (pintype "bidirectional"))
      (node (ref "R54") (pin "1") (pinfunction "1_1") (pintype "passive"))
    )
    (net (code "64") (name "Net-(CN3-8)") (class "Default")
      (node (ref "CN3") (pin "P$8") (pinfunction "8_P$8") (pintype "bidirectional"))
      (node (ref "R25") (pin "1") (pinfunction "1_1") (pintype "passive"))
    )
    (net (code "65") (name "Net-(CN3-9)") (class "Default")
      (node (ref "CN3") (pin "P$9") (pinfunction "9_P$9") (pintype "bidirectional"))
      (node (ref "R53") (pin "1") (pinfunction "1_1") (pintype "passive"))
    )
    (net (code "66") (name "Net-(CN3-10)") (class "Default")
      (node (ref "CN3") (pin "P$10") (pinfunction "10_P$10") (pintype "bidirectional"))
      (node (ref "R24") (pin "1") (pinfunction "1_1") (pintype "passive"))
    )
    (net (code "67") (name "Net-(CN3-11)") (class "Default")
      (node (ref "CN3") (pin "P$11") (pinfunction "11_P$11") (pintype "bidirectional"))
      (node (ref "R52") (pin "1") (pinfunction "1_1") (pintype "passive"))
    )
    (net (code "68") (name "Net-(CN3-12)") (class "Default")
      (node (ref "CN3") (pin "P$12") (pinfunction "12_P$12") (pintype "bidirectional"))
      (node (ref "R23") (pin "1") (pinfunction "1_1") (pintype "passive"))
    )
    (net (code "69") (name "Net-(CN3-13)") (class "Default")
      (node (ref "CN3") (pin "P$13") (pinfunction "13_P$13") (pintype "bidirectional"))
      (node (ref "R51") (pin "1") (pinfunction "1_1") (pintype "passive"))
    )
    (net (code "70") (name "Net-(CN3-14)") (class "Default")
      (node (ref "CN3") (pin "P$14") (pinfunction "14_P$14") (pintype "bidirectional"))
      (node (ref "R22") (pin "1") (pinfunction "1_1") (pintype "passive"))
    )
    (net (code "71") (name "Net-(CN3-15)") (class "Default")
      (node (ref "CN3") (pin "P$15") (pinfunction "15_P$15") (pintype "bidirectional"))
      (node (ref "R50") (pin "1") (pinfunction "1_1") (pintype "passive"))
    )
    (net (code "72") (name "Net-(CN3-16)") (class "Default")
      (node (ref "CN3") (pin "P$16") (pinfunction "16_P$16") (pintype "bidirectional"))
      (node (ref "R14") (pin "1") (pinfunction "1_1") (pintype "passive"))
    )
    (net (code "73") (name "Net-(CN3-17)") (class "Default")
      (node (ref "CN3") (pin "P$17") (pinfunction "17_P$17") (pintype "bidirectional"))
      (node (ref "R42") (pin "1") (pinfunction "1_1") (pintype "passive"))
    )
    (net (code "74") (name "Net-(CN3-18)") (class "Default")
      (node (ref "CN3") (pin "P$18") (pinfunction "18_P$18") (pintype "bidirectional"))
      (node (ref "R13") (pin "1") (pinfunction "1_1") (pintype "passive"))
    )
    (net (code "75") (name "Net-(CN3-19)") (class "Default")
      (node (ref "CN3") (pin "P$19") (pinfunction "19_P$19") (pintype "bidirectional"))
      (node (ref "R41") (pin "1") (pinfunction "1_1") (pintype "passive"))
    )
    (net (code "76") (name "Net-(CN3-20)") (class "Default")
      (node (ref "CN3") (pin "P$20") (pinfunction "20_P$20") (pintype "bidirectional"))
      (node (ref "R12") (pin "1") (pinfunction "1_1") (pintype "passive"))
    )
    (net (code "77") (name "Net-(CN3-21)") (class "Default")
      (node (ref "CN3") (pin "P$21") (pinfunction "21_P$21") (pintype "bidirectional"))
      (node (ref "R40") (pin "1") (pinfunction "1_1") (pintype "passive"))
    )
    (net (code "78") (name "Net-(CN3-22)") (class "Default")
      (node (ref "CN3") (pin "P$22") (pinfunction "22_P$22") (pintype "bidirectional"))
      (node (ref "R11") (pin "1") (pinfunction "1_1") (pintype "passive"))
    )
    (net (code "79") (name "Net-(CN3-23)") (class "Default")
      (node (ref "CN3") (pin "P$23") (pinfunction "23_P$23") (pintype "bidirectional"))
      (node (ref "R39") (pin "1") (pinfunction "1_1") (pintype "passive"))
    )
    (net (code "80") (name "Net-(CN3-24)") (class "Default")
      (node (ref "CN3") (pin "P$24") (pinfunction "24_P$24") (pintype "bidirectional"))
      (node (ref "R10") (pin "1") (pinfunction "1_1") (pintype "passive"))
    )
    (net (code "81") (name "Net-(CN3-25)") (class "Default")
      (node (ref "CN3") (pin "P$25") (pinfunction "25_P$25") (pintype "bidirectional"))
      (node (ref "R38") (pin "1") (pinfunction "1_1") (pintype "passive"))
    )
    (net (code "82") (name "Net-(CN3-26)") (class "Default")
      (node (ref "CN3") (pin "P$26") (pinfunction "26_P$26") (pintype "bidirectional"))
      (node (ref "R9") (pin "1") (pinfunction "1_1") (pintype "passive"))
    )
    (net (code "83") (name "Net-(CN3-27)") (class "Default")
      (node (ref "CN3") (pin "P$27") (pinfunction "27_P$27") (pintype "bidirectional"))
      (node (ref "R37") (pin "1") (pinfunction "1_1") (pintype "passive"))
    )
    (net (code "84") (name "Net-(CN3-28)") (class "Default")
      (node (ref "CN3") (pin "P$28") (pinfunction "28_P$28") (pintype "bidirectional"))
      (node (ref "R8") (pin "1") (pinfunction "1_1") (pintype "passive"))
    )
    (net (code "85") (name "Net-(CN3-29)") (class "Default")
      (node (ref "CN3") (pin "P$29") (pinfunction "29_P$29") (pintype "bidirectional"))
      (node (ref "R36") (pin "1") (pinfunction "1_1") (pintype "passive"))
    )
    (net (code "86") (name "Net-(Q1-B)") (class "Default")
      (node (ref "Q1") (pin "2") (pinfunction "B_2") (pintype "passive"))
      (node (ref "R8") (pin "2") (pinfunction "2_2") (pintype "passive"))
    )
    (net (code "87") (name "Net-(Q1-C)") (class "Default")
      (node (ref "Q1") (pin "3") (pinfunction "C_3") (pintype "passive"))
      (node (ref "R1") (pin "1") (pinfunction "1_1") (pintype "passive"))
    )
    (net (code "88") (name "Net-(Q2-B)") (class "Default")
      (node (ref "Q2") (pin "2") (pinfunction "B_2") (pintype "passive"))
      (node (ref "R9") (pin "2") (pinfunction "2_2") (pintype "passive"))
    )
    (net (code "89") (name "Net-(Q2-C)") (class "Default")
      (node (ref "Q2") (pin "3") (pinfunction "C_3") (pintype "passive"))
      (node (ref "R2") (pin "1") (pinfunction "1_1") (pintype "passive"))
    )
    (net (code "90") (name "Net-(Q3-B)") (class "Default")
      (node (ref "Q3") (pin "2") (pinfunction "B_2") (pintype "passive"))
      (node (ref "R10") (pin "2") (pinfunction "2_2") (pintype "passive"))
    )
    (net (code "91") (name "Net-(Q3-C)") (class "Default")
      (node (ref "Q3") (pin "3") (pinfunction "C_3") (pintype "passive"))
      (node (ref "R3") (pin "1") (pinfunction "1_1") (pintype "passive"))
    )
    (net (code "92") (name "Net-(Q4-B)") (class "Default")
      (node (ref "Q4") (pin "2") (pinfunction "B_2") (pintype "passive"))
      (node (ref "R11") (pin "2") (pinfunction "2_2") (pintype "passive"))
    )
    (net (code "93") (name "Net-(Q4-C)") (class "Default")
      (node (ref "Q4") (pin "3") (pinfunction "C_3") (pintype "passive"))
      (node (ref "R4") (pin "1") (pinfunction "1_1") (pintype "passive"))
    )
    (net (code "94") (name "Net-(Q5-B)") (class "Default")
      (node (ref "Q5") (pin "2") (pinfunction "B_2") (pintype "passive"))
      (node (ref "R12") (pin "2") (pinfunction "2_2") (pintype "passive"))
    )
    (net (code "95") (name "Net-(Q5-C)") (class "Default")
      (node (ref "Q5") (pin "3") (pinfunction "C_3") (pintype "passive"))
      (node (ref "R5") (pin "1") (pinfunction "1_1") (pintype "passive"))
    )
    (net (code "96") (name "Net-(Q6-B)") (class "Default")
      (node (ref "Q6") (pin "2") (pinfunction "B_2") (pintype "passive"))
      (node (ref "R13") (pin "2") (pinfunction "2_2") (pintype "passive"))
    )
    (net (code "97") (name "Net-(Q6-C)") (class "Default")
      (node (ref "Q6") (pin "3") (pinfunction "C_3") (pintype "passive"))
      (node (ref "R6") (pin "1") (pinfunction "1_1") (pintype "passive"))
    )
    (net (code "98") (name "Net-(Q7-B)") (class "Default")
      (node (ref "Q7") (pin "2") (pinfunction "B_2") (pintype "passive"))
      (node (ref "R14") (pin "2") (pinfunction "2_2") (pintype "passive"))
    )
    (net (code "99") (name "Net-(Q7-C)") (class "Default")
      (node (ref "Q7") (pin "3") (pinfunction "C_3") (pintype "passive"))
      (node (ref "R7") (pin "1") (pinfunction "1_1") (pintype "passive"))
    )
    (net (code "100") (name "Net-(Q8-B)") (class "Default")
      (node (ref "Q8") (pin "2") (pinfunction "B_2") (pintype "passive"))
      (node (ref "R22") (pin "2") (pinfunction "2_2") (pintype "passive"))
    )
    (net (code "101") (name "Net-(Q8-C)") (class "Default")
      (node (ref "Q8") (pin "3") (pinfunction "C_3") (pintype "passive"))
      (node (ref "R15") (pin "1") (pinfunction "1_1") (pintype "passive"))
    )
    (net (code "102") (name "Net-(Q9-B)") (class "Default")
      (node (ref "Q9") (pin "2") (pinfunction "B_2") (pintype "passive"))
      (node (ref "R23") (pin "2") (pinfunction "2_2") (pintype "passive"))
    )
    (net (code "103") (name "Net-(Q9-C)") (class "Default")
      (node (ref "Q9") (pin "3") (pinfunction "C_3") (pintype "passive"))
      (node (ref "R16") (pin "1") (pinfunction "1_1") (pintype "passive"))
    )
    (net (code "104") (name "Net-(Q10-B)") (class "Default")
      (node (ref "Q10") (pin "2") (pinfunction "B_2") (pintype "passive"))
      (node (ref "R24") (pin "2") (pinfunction "2_2") (pintype "passive"))
    )
    (net (code "105") (name "Net-(Q10-C)") (class "Default")
      (node (ref "Q10") (pin "3") (pinfunction "C_3") (pintype "passive"))
      (node (ref "R17") (pin "1") (pinfunction "1_1") (pintype "passive"))
    )
    (net (code "106") (name "Net-(Q11-B)") (class "Default")
      (node (ref "Q11") (pin "2") (pinfunction "B_2") (pintype "passive"))
      (node (ref "R25") (pin "2") (pinfunction "2_2") (pintype "passive"))
    )
    (net (code "107") (name "Net-(Q11-C)") (class "Default")
      (node (ref "Q11") (pin "3") (pinfunction "C_3") (pintype "passive"))
      (node (ref "R18") (pin "1") (pinfunction "1_1") (pintype "passive"))
    )
    (net (code "108") (name "Net-(Q12-B)") (class "Default")
      (node (ref "Q12") (pin "2") (pinfunction "B_2") (pintype "passive"))
      (node (ref "R26") (pin "2") (pinfunction "2_2") (pintype "passive"))
    )
    (net (code "109") (name "Net-(Q12-C)") (class "Default")
      (node (ref "Q12") (pin "3") (pinfunction "C_3") (pintype "passive"))
      (node (ref "R19") (pin "1") (pinfunction "1_1") (pintype "passive"))
    )
    (net (code "110") (name "Net-(Q13-B)") (class "Default")
      (node (ref "Q13") (pin "2") (pinfunction "B_2") (pintype "passive"))
      (node (ref "R27") (pin "2") (pinfunction "2_2") (pintype "passive"))
    )
    (net (code "111") (name "Net-(Q13-C)") (class "Default")
      (node (ref "Q13") (pin "3") (pinfunction "C_3") (pintype "passive"))
      (node (ref "R20") (pin "1") (pinfunction "1_1") (pintype "passive"))
    )
    (net (code "112") (name "Net-(Q14-B)") (class "Default")
      (node (ref "Q14") (pin "2") (pinfunction "B_2") (pintype "passive"))
      (node (ref "R28") (pin "2") (pinfunction "2_2") (pintype "passive"))
    )
    (net (code "113") (name "Net-(Q14-C)") (class "Default")
      (node (ref "Q14") (pin "3") (pinfunction "C_3") (pintype "passive"))
      (node (ref "R21") (pin "1") (pinfunction "1_1") (pintype "passive"))
    )
    (net (code "114") (name "Net-(Q15-B)") (class "Default")
      (node (ref "Q15") (pin "2") (pinfunction "B_2") (pintype "passive"))
      (node (ref "R36") (pin "2") (pinfunction "2_2") (pintype "passive"))
    )
    (net (code "115") (name "Net-(Q15-C)") (class "Default")
      (node (ref "Q15") (pin "3") (pinfunction "C_3") (pintype "passive"))
      (node (ref "R29") (pin "1") (pinfunction "1_1") (pintype "passive"))
    )
    (net (code "116") (name "Net-(Q16-B)") (class "Default")
      (node (ref "Q16") (pin "2") (pinfunction "B_2") (pintype "passive"))
      (node (ref "R37") (pin "2") (pinfunction "2_2") (pintype "passive"))
    )
    (net (code "117") (name "Net-(Q16-C)") (class "Default")
      (node (ref "Q16") (pin "3") (pinfunction "C_3") (pintype "passive"))
      (node (ref "R30") (pin "1") (pinfunction "1_1") (pintype "passive"))
    )
    (net (code "118") (name "Net-(Q17-B)") (class "Default")
      (node (ref "Q17") (pin "2") (pinfunction "B_2") (pintype "passive"))
      (node (ref "R38") (pin "2") (pinfunction "2_2") (pintype "passive"))
    )
    (net (code "119") (name "Net-(Q17-C)") (class "Default")
      (node (ref "Q17") (pin "3") (pinfunction "C_3") (pintype "passive"))
      (node (ref "R31") (pin "1") (pinfunction "1_1") (pintype "passive"))
    )
    (net (code "120") (name "Net-(Q18-B)") (class "Default")
      (node (ref "Q18") (pin "2") (pinfunction "B_2") (pintype "passive"))
      (node (ref "R39") (pin "2") (pinfunction "2_2") (pintype "passive"))
    )
    (net (code "121") (name "Net-(Q18-C)") (class "Default")
      (node (ref "Q18") (pin "3") (pinfunction "C_3") (pintype "passive"))
      (node (ref "R32") (pin "1") (pinfunction "1_1") (pintype "passive"))
    )
    (net (code "122") (name "Net-(Q19-B)") (class "Default")
      (node (ref "Q19") (pin "2") (pinfunction "B_2") (pintype "passive"))
      (node (ref "R40") (pin "2") (pinfunction "2_2") (pintype "passive"))
    )
    (net (code "123") (name "Net-(Q19-C)") (class "Default")
      (node (ref "Q19") (pin "3") (pinfunction "C_3") (pintype "passive"))
      (node (ref "R33") (pin "1") (pinfunction "1_1") (pintype "passive"))
    )
    (net (code "124") (name "Net-(Q20-B)") (class "Default")
      (node (ref "Q20") (pin "2") (pinfunction "B_2") (pintype "passive"))
      (node (ref "R41") (pin "2") (pinfunction "2_2") (pintype "passive"))
    )
    (net (code "125") (name "Net-(Q20-C)") (class "Default")
      (node (ref "Q20") (pin "3") (pinfunction "C_3") (pintype "passive"))
      (node (ref "R34") (pin "1") (pinfunction "1_1") (pintype "passive"))
    )
    (net (code "126") (name "Net-(Q21-B)") (class "Default")
      (node (ref "Q21") (pin "2") (pinfunction "B_2") (pintype "passive"))
      (node (ref "R42") (pin "2") (pinfunction "2_2") (pintype "passive"))
    )
    (net (code "127") (name "Net-(Q21-C)") (class "Default")
      (node (ref "Q21") (pin "3") (pinfunction "C_3") (pintype "passive"))
      (node (ref "R35") (pin "1") (pinfunction "1_1") (pintype "passive"))
    )
    (net (code "128") (name "Net-(Q22-B)") (class "Default")
      (node (ref "Q22") (pin "2") (pinfunction "B_2") (pintype "passive"))
      (node (ref "R50") (pin "2") (pinfunction "2_2") (pintype "passive"))
    )
    (net (code "129") (name "Net-(Q22-C)") (class "Default")
      (node (ref "Q22") (pin "3") (pinfunction "C_3") (pintype "passive"))
      (node (ref "R43") (pin "1") (pinfunction "1_1") (pintype "passive"))
    )
    (net (code "130") (name "Net-(Q23-B)") (class "Default")
      (node (ref "Q23") (pin "2") (pinfunction "B_2") (pintype "passive"))
      (node (ref "R51") (pin "2") (pinfunction "2_2") (pintype "passive"))
    )
    (net (code "131") (name "Net-(Q23-C)") (class "Default")
      (node (ref "Q23") (pin "3") (pinfunction "C_3") (pintype "passive"))
      (node (ref "R44") (pin "1") (pinfunction "1_1") (pintype "passive"))
    )
    (net (code "132") (name "Net-(Q24-B)") (class "Default")
      (node (ref "Q24") (pin "2") (pinfunction "B_2") (pintype "passive"))
      (node (ref "R52") (pin "2") (pinfunction "2_2") (pintype "passive"))
    )
    (net (code "133") (name "Net-(Q24-C)") (class "Default")
      (node (ref "Q24") (pin "3") (pinfunction "C_3") (pintype "passive"))
      (node (ref "R45") (pin "1") (pinfunction "1_1") (pintype "passive"))
    )
    (net (code "134") (name "Net-(Q25-B)") (class "Default")
      (node (ref "Q25") (pin "2") (pinfunction "B_2") (pintype "passive"))
      (node (ref "R53") (pin "2") (pinfunction "2_2") (pintype "passive"))
    )
    (net (code "135") (name "Net-(Q25-C)") (class "Default")
      (node (ref "Q25") (pin "3") (pinfunction "C_3") (pintype "passive"))
      (node (ref "R46") (pin "1") (pinfunction "1_1") (pintype "passive"))
    )
    (net (code "136") (name "Net-(Q26-B)") (class "Default")
      (node (ref "Q26") (pin "2") (pinfunction "B_2") (pintype "passive"))
      (node (ref "R54") (pin "2") (pinfunction "2_2") (pintype "passive"))
    )
    (net (code "137") (name "Net-(Q26-C)") (class "Default")
      (node (ref "Q26") (pin "3") (pinfunction "C_3") (pintype "passive"))
      (node (ref "R47") (pin "1") (pinfunction "1_1") (pintype "passive"))
    )
    (net (code "138") (name "Net-(Q27-B)") (class "Default")
      (node (ref "Q27") (pin "2") (pinfunction "B_2") (pintype "passive"))
      (node (ref "R55") (pin "2") (pinfunction "2_2") (pintype "passive"))
    )
    (net (code "139") (name "Net-(Q27-C)") (class "Default")
      (node (ref "Q27") (pin "3") (pinfunction "C_3") (pintype "passive"))
      (node (ref "R48") (pin "1") (pinfunction "1_1") (pintype "passive"))
    )
    (net (code "140") (name "Net-(Q28-B)") (class "Default")
      (node (ref "Q28") (pin "2") (pinfunction "B_2") (pintype "passive"))
      (node (ref "R56") (pin "2") (pinfunction "2_2") (pintype "passive"))
    )
    (net (code "141") (name "Net-(Q28-C)") (class "Default")
      (node (ref "Q28") (pin "3") (pinfunction "C_3") (pintype "passive"))
      (node (ref "R49") (pin "1") (pinfunction "1_1") (pintype "passive"))
    )
    (net (code "142") (name "unconnected-(CN2-1-PadP$1)") (class "Default")
      (node (ref "CN2") (pin "P$1") (pinfunction "1_P$1") (pintype "bidirectional"))
    )
    (net (code "143") (name "unconnected-(CN2-16-PadP$16)") (class "Default")
      (node (ref "CN2") (pin "P$16") (pinfunction "16_P$16") (pintype "bidirectional"))
    )
    (net (code "144") (name "unconnected-(CN2-30-PadP$30)") (class "Default")
      (node (ref "CN2") (pin "P$30") (pinfunction "30_P$30") (pintype "bidirectional"))
    )
    (net (code "145") (name "unconnected-(CN3-1-PadP$1)") (class "Default")
      (node (ref "CN3") (pin "P$1") (pinfunction "1_P$1") (pintype "bidirectional"))
    )
    (net (code "146") (name "unconnected-(CN3-30-PadP$30)") (class "Default")
      (node (ref "CN3") (pin "P$30") (pinfunction "30_P$30") (pintype "bidirectional"))
    )
    (net (code "147") (name "unconnected-(R7-Pad2)") (class "Default")
      (node (ref "R7") (pin "2") (pinfunction "2_2") (pintype "passive"))
    )
  )
)
